# 1.net
KiCad netlist of a schematic drawn in Altium Designer
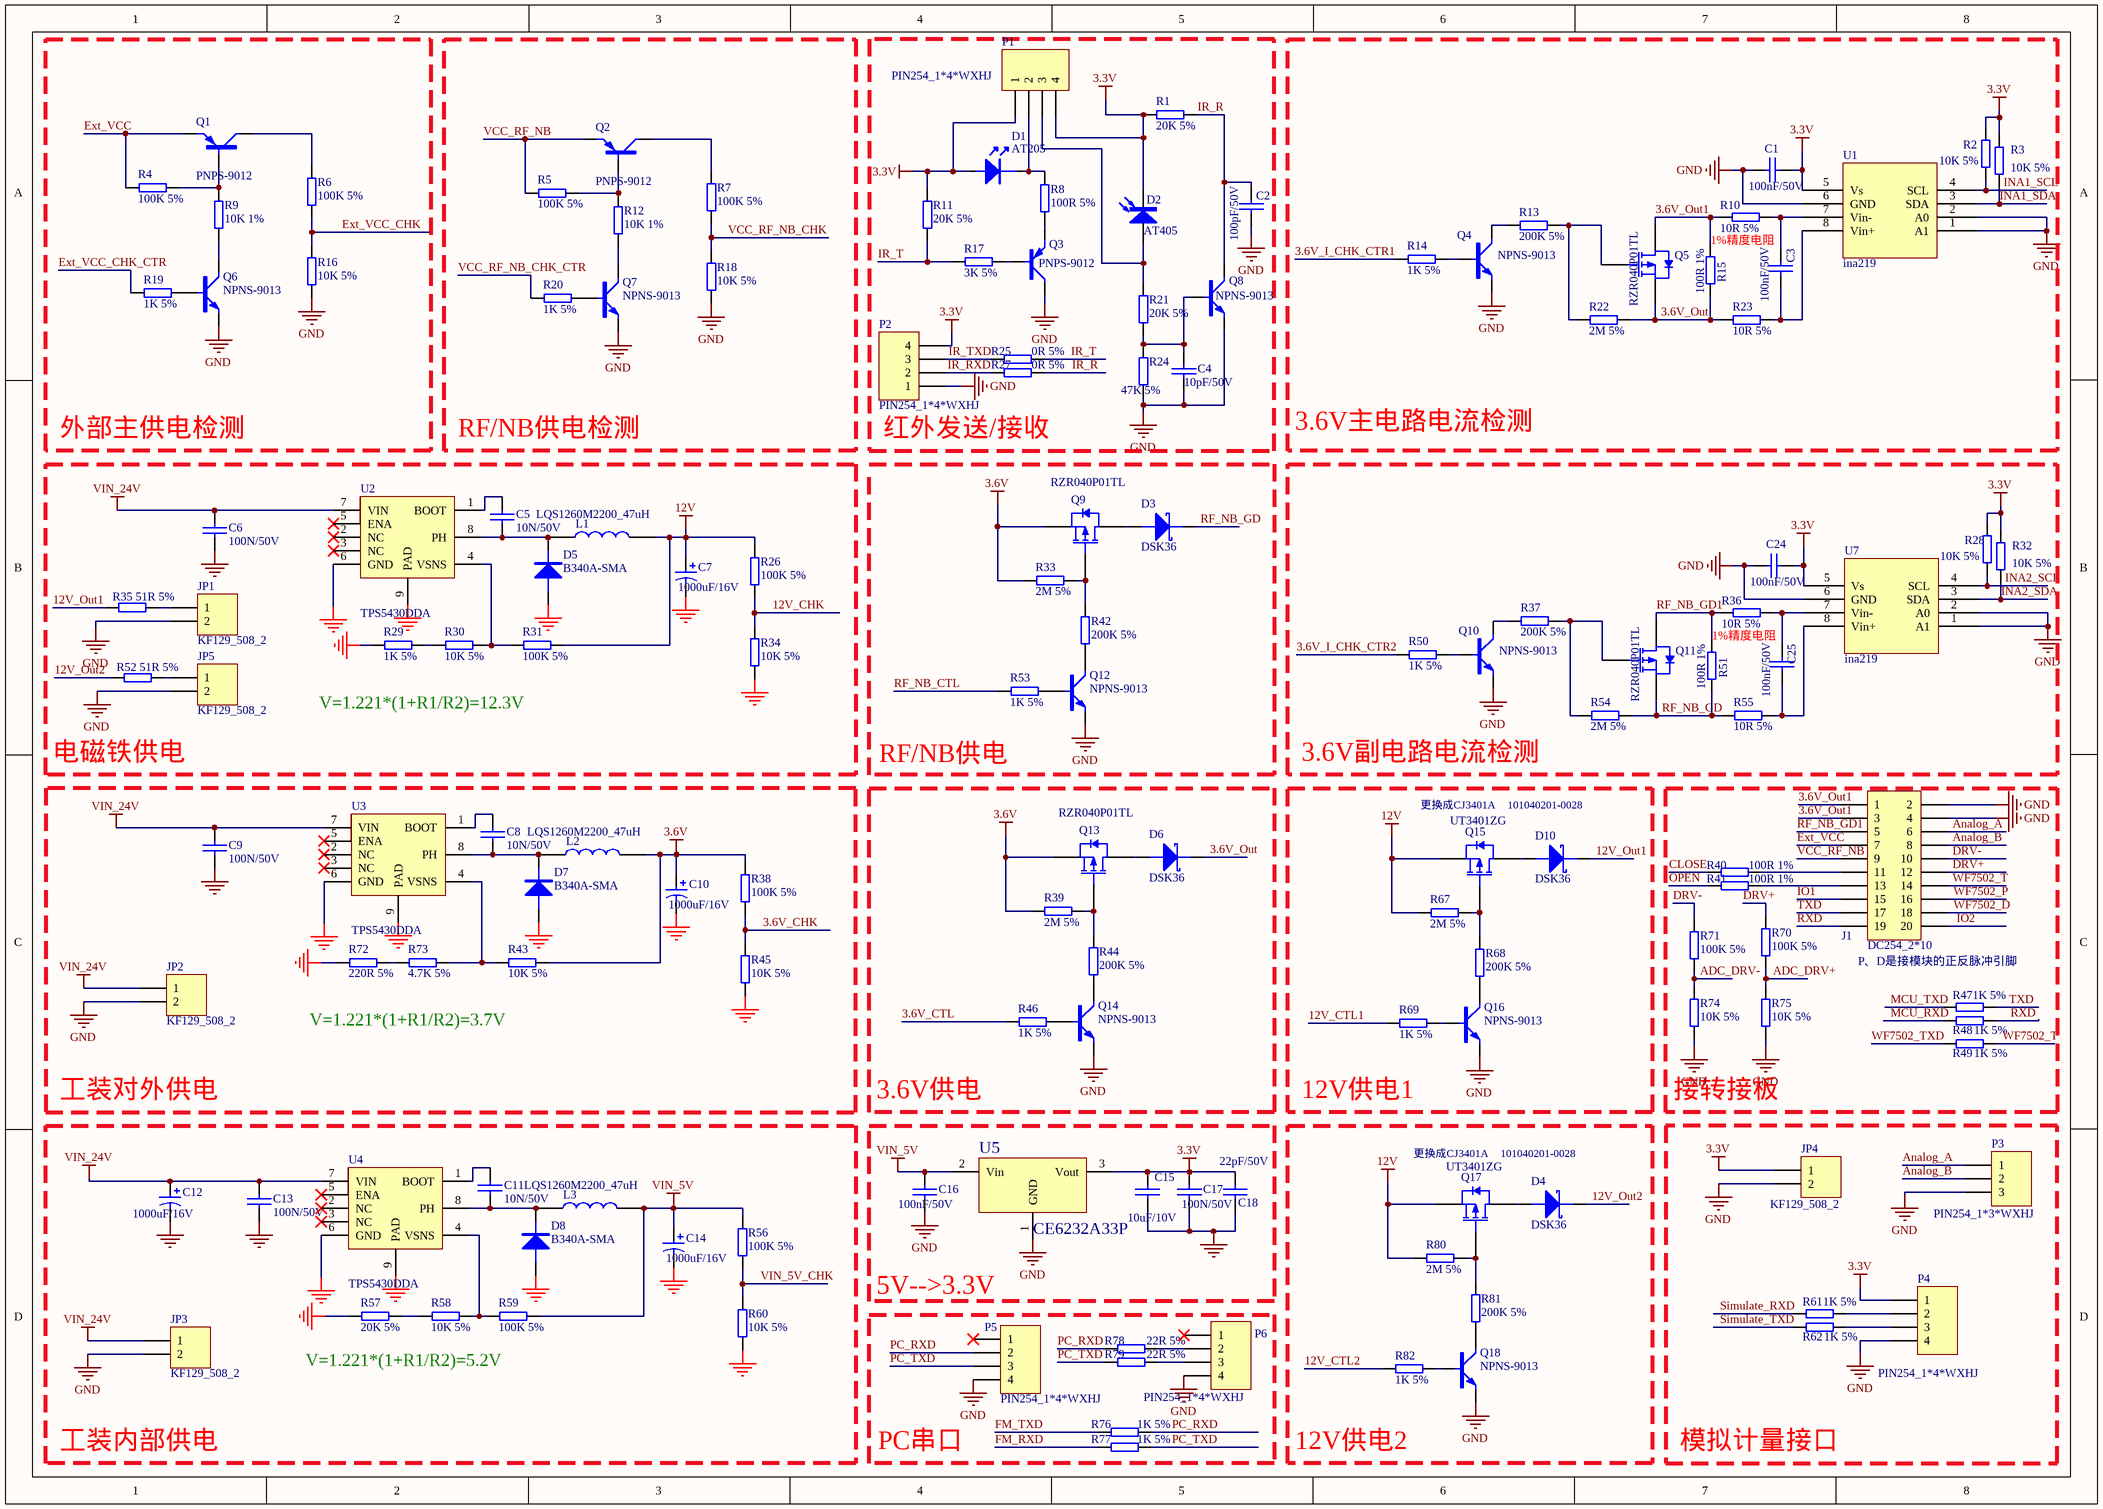
[diagram p0: 水表通用工装一版1.SchDoc]

(export (version "E")
  (design (tool "Eeschema 10.0.6"))
  (components
    (comp (ref "C1")
      (value "100nF/50V")
      (footprint "CAP0603")
      (description "104pF,50 V,±10%,0603,国巨,CC0603KRX7R9BB104")
      (fields (field (name "PART NUMBER") "101020103-0021"))
      (libsource (lib "Database_Libs2") (part "CC03K7R9_100N"))
    )
    (comp (ref "C2")
      (value "100pF/50V")
      (footprint "CAP0603")
      (description "101pf,50 V,±5%,0603,国巨,CC0603JRNP09BN101")
      (fields (field (name "PART NUMBER") "101020103-0010"))
      (libsource (lib "Database_Libs2") (part "CC03JPO9_101P"))
    )
    (comp (ref "C3")
      (value "100nF/50V")
      (footprint "CAP0603")
      (description "104pF,50 V,±10%,0603,国巨,CC0603KRX7R9BB104")
      (fields (field (name "PART NUMBER") "101020103-0021"))
      (libsource (lib "Database_Libs2") (part "CC03K7R9_100N"))
    )
    (comp (ref "C4")
      (value "10pF/50V")
      (footprint "CAP0603")
      (description "10pF,50 V,±5%,0603,X7R,国巨,CC0603JRNPO9BN100")
      (fields (field (name "PART NUMBER") "101020103-0014"))
      (libsource (lib "Database_Libs2") (part "CC03JPO9_10P"))
    )
    (comp (ref "C5")
      (value "10N/50V")
      (footprint "CAP0603")
      (description "10N/50V，±10%，0603")
      (fields (field (name "PART NUMBER") "101020103-0007"))
      (libsource (lib "Database_Libs1") (part "CC03K7R9B_10N"))
    )
    (comp (ref "C6")
      (value "100N/50V")
      (footprint "CAP0603")
      (description "100N/50V，±10%，0603")
      (fields (field (name "PART NUMBER") "101020103-0021"))
      (libsource (lib "Database_Libs1") (part "CC03K7R9B_100N"))
    )
    (comp (ref "C7")
      (value "1000uF/16V")
      (footprint "CAPPC_350_800_1600")
      (description "1000uF,16 V,±20%,8*20mm,Rubycon,16ZLH1000M")
      (fields (field (name "PART NUMBER") "1010203-0029"))
      (libsource (lib "Database_Libs2") (part "CAL7MRZLH_1000U_R"))
    )
    (comp (ref "C8")
      (value "10N/50V")
      (footprint "CAP0603")
      (description "10N/50V，±10%，0603")
      (fields (field (name "PART NUMBER") "101020103-0007"))
      (libsource (lib "Database_Libs1") (part "CC03K7R9B_10N"))
    )
    (comp (ref "C9")
      (value "100N/50V")
      (footprint "CAP0603")
      (description "100N/50V，±10%，0603")
      (fields (field (name "PART NUMBER") "101020103-0021"))
      (libsource (lib "Database_Libs1") (part "CC03K7R9B_100N"))
    )
    (comp (ref "C10")
      (value "1000uF/16V")
      (footprint "CAPPC_350_800_1600")
      (description "1000uF,16 V,±20%,8*20mm,Rubycon,16ZLH1000M")
      (fields (field (name "PART NUMBER") "1010203-0029"))
      (libsource (lib "Database_Libs2") (part "CAL7MRZLH_1000U_R"))
    )
    (comp (ref "C11")
      (value "10N/50V")
      (footprint "CAP0603")
      (description "10N/50V，±10%，0603")
      (fields (field (name "PART NUMBER") "101020103-0007"))
      (libsource (lib "Database_Libs1") (part "CC03K7R9B_10N"))
    )
    (comp (ref "C12")
      (value "1000uF/16V")
      (footprint "CAPPC_350_800_1600")
      (description "1000uF,16 V,±20%,8*20mm,Rubycon,16ZLH1000M")
      (fields (field (name "PART NUMBER") "1010203-0029"))
      (libsource (lib "Database_Libs2") (part "CAL7MRZLH_1000U_R"))
    )
    (comp (ref "C13")
      (value "100N/50V")
      (footprint "CAP0603")
      (description "100N/50V，±10%，0603")
      (fields (field (name "PART NUMBER") "101020103-0021"))
      (libsource (lib "Database_Libs1") (part "CC03K7R9B_100N"))
    )
    (comp (ref "C14")
      (value "1000uF/16V")
      (footprint "CAPPC_350_800_1600")
      (description "1000uF,16 V,±20%,8*20mm,Rubycon,16ZLH1000M")
      (fields (field (name "PART NUMBER") "1010203-0029"))
      (libsource (lib "Database_Libs2") (part "CAL7MRZLH_1000U_R"))
    )
    (comp (ref "C15")
      (value "10uF/10V")
      (footprint "CAP0603")
      (description "106pF,10 V,±10%,0603,村田,GRM188R61A106KE47D")
      (fields (field (name "PART NUMBER") "101020103-0026"))
      (libsource (lib "Database_Libs2") (part "CC03K5R6_10U"))
    )
    (comp (ref "C16")
      (value "100nF/50V")
      (footprint "CAP0603")
      (description "104pF,50 V,±10%,0603,国巨,CC0603KRX7R9BB104")
      (fields (field (name "PART NUMBER") "101020103-0021"))
      (libsource (lib "Database_Libs2") (part "CC03K7R9_100N"))
    )
    (comp (ref "C17")
      (value "100N/50V")
      (footprint "CAP0603")
      (description "100N/50V，±10%，0603")
      (fields (field (name "PART NUMBER") "101020103-0021"))
      (libsource (lib "Database_Libs2") (part "CC03K7R9B_100N"))
    )
    (comp (ref "C18")
      (value "22pF/50V")
      (footprint "CAP0603")
      (description "22pF,50 V,±5%,0603,国巨,CC0603JRNPO9BN22")
      (fields (field (name "PART NUMBER") "101020103-0009"))
      (libsource (lib "Database_Libs2") (part "CC03JPO9_22P"))
    )
    (comp (ref "C24")
      (value "100nF/50V")
      (footprint "CAP0603")
      (description "104pF,50 V,±10%,0603,国巨,CC0603KRX7R9BB104")
      (fields (field (name "PART NUMBER") "101020103-0021"))
      (libsource (lib "Database_Libs2") (part "CC03K7R9_100N"))
    )
    (comp (ref "C25")
      (value "100nF/50V")
      (footprint "CAP0603")
      (description "104pF,50 V,±10%,0603,国巨,CC0603KRX7R9BB104")
      (fields (field (name "PART NUMBER") "101020103-0021"))
      (libsource (lib "Database_Libs2") (part "CC03K7R9_100N"))
    )
    (comp (ref "D1") (value "AT205") (footprint "AT205/405") (libsource (lib "Schlib1") (part "AT205")))
    (comp (ref "D2")
      (value "AT405")
      (footprint "AT205/405")
      (description "红外接收头，插件，红光，AT405_PD_01")
      (fields (field (name "PART NUMBER") "101040102-0011") (field (name "MANUFACTURER") "品观"))
      (libsource (lib "Devices") (part "LED_IN"))
    )
    (comp (ref "D3")
      (value "DSK36")
      (footprint "SOD-123FL")
      (description "DSK14,SOD-123FL,1 A,40 V,28 V,台湾强茂集团苏州群鑫电子,DSK14")
      (fields (field (name "PART NUMBER") "101040101-0043"))
      (libsource (lib "Database_Libs2") (part "02_DSK14"))
    )
    (comp (ref "D4")
      (value "DSK36")
      (footprint "SOD-123FL")
      (description "DSK14,SOD-123FL,1 A,40 V,28 V,台湾强茂集团苏州群鑫电子,DSK14")
      (fields (field (name "PART NUMBER") "101040101-0043"))
      (libsource (lib "Database_Libs2") (part "02_DSK14"))
    )
    (comp (ref "D5")
      (value "B340A-SMA")
      (footprint "DO-214AC")
      (fields (field (name "PART NUMBER") "101040101-0014"))
      (libsource (lib "Database_Libs1") (part "02_B340A-SMA"))
    )
    (comp (ref "D6")
      (value "DSK36")
      (footprint "SOD-123FL")
      (description "DSK14,SOD-123FL,1 A,40 V,28 V,台湾强茂集团苏州群鑫电子,DSK14")
      (fields (field (name "PART NUMBER") "101040101-0043"))
      (libsource (lib "Database_Libs2") (part "02_DSK14"))
    )
    (comp (ref "D7")
      (value "B340A-SMA")
      (footprint "DO-214AC")
      (fields (field (name "PART NUMBER") "101040101-0014"))
      (libsource (lib "Database_Libs1") (part "02_B340A-SMA"))
    )
    (comp (ref "D8")
      (value "B340A-SMA")
      (footprint "DO-214AC")
      (fields (field (name "PART NUMBER") "101040101-0014"))
      (libsource (lib "Database_Libs1") (part "02_B340A-SMA"))
    )
    (comp (ref "D10")
      (value "DSK36")
      (footprint "SOD-123FL")
      (description "DSK14,SOD-123FL,1 A,40 V,28 V,台湾强茂集团苏州群鑫电子,DSK14")
      (fields (field (name "PART NUMBER") "101040101-0043"))
      (libsource (lib "Database_Libs2") (part "02_DSK14"))
    )
    (comp (ref "J1")
      (value "DC254_2*10")
      (footprint "DC254_2*10")
      (description "DC2 2.54mm 2x10pin,2.54mm间距，2x10pin，32×8.55×27.5mm,母头,双排,双排牛角座")
      (fields (field (name "PART NUMBER") "1010902-0139"))
      (libsource (lib "Database_Libs2") (part "DC254_2*10"))
    )
    (comp (ref "JP1")
      (value "KF129_508_2")
      (footprint "KF129_508_2")
      (description "KF129-2P,螺丝紧固,2,ABS,松涛")
      (fields (field (name "PART NUMBER") "1010904-0015"))
      (libsource (lib "Database_Libs2") (part "KF129_508_2"))
    )
    (comp (ref "JP2")
      (value "KF129_508_2")
      (footprint "KF129_508_2")
      (description "KF129-2P,螺丝紧固,2,ABS,松涛")
      (fields (field (name "PART NUMBER") "1010904-0015"))
      (libsource (lib "Database_Libs2") (part "KF129_508_2"))
    )
    (comp (ref "JP3")
      (value "KF129_508_2")
      (footprint "KF129_508_2")
      (description "KF129-2P,螺丝紧固,2,ABS,松涛")
      (fields (field (name "PART NUMBER") "1010904-0015"))
      (libsource (lib "Database_Libs2") (part "KF129_508_2"))
    )
    (comp (ref "JP4")
      (value "KF129_508_2")
      (footprint "KF129_508_2")
      (description "KF129-2P,螺丝紧固,2,ABS,松涛")
      (fields (field (name "PART NUMBER") "1010904-0015"))
      (libsource (lib "Database_Libs2") (part "KF129_508_2"))
    )
    (comp (ref "JP5")
      (value "KF129_508_2")
      (footprint "KF129_508_2")
      (description "KF129-2P,螺丝紧固,2,ABS,松涛")
      (fields (field (name "PART NUMBER") "1010904-0015"))
      (libsource (lib "Database_Libs2") (part "KF129_508_2"))
    )
    (comp (ref "L1")
      (value "LQS1260M2200_47uH")
      (footprint "LQS1212")
      (description "47uH/2.2A,±20%，0.072Ω，L1200X1200X600")
      (fields (field (name "PART NUMBER") "1010302-0007"))
      (libsource (lib "Database_Libs1") (part "06_LQS1260M2200_47uH"))
    )
    (comp (ref "L2")
      (value "LQS1260M2200_47uH")
      (footprint "LQS1212")
      (description "47uH/2.2A,±20%，0.072Ω，L1200X1200X600")
      (fields (field (name "PART NUMBER") "1010302-0007"))
      (libsource (lib "Database_Libs1") (part "06_LQS1260M2200_47uH"))
    )
    (comp (ref "L3")
      (value "LQS1260M2200_47uH")
      (footprint "LQS1212")
      (description "47uH/2.2A,±20%，0.072Ω，L1200X1200X600")
      (fields (field (name "PART NUMBER") "1010302-0007"))
      (libsource (lib "Database_Libs1") (part "06_LQS1260M2200_47uH"))
    )
    (comp (ref "P1")
      (value "PIN254_1*4*WXHJ")
      (footprint "PIN254_1*4*1100S")
      (description "1*4 ，Φ1.0 ，2.54mm，直脚,无需焊接器件")
      (fields (field (name "PART NUMBER") "AD_WXHJ_PinHeader_01"))
      (libsource (lib "Database_Libs2") (part "PIN254_1*4*1100S"))
    )
    (comp (ref "P2")
      (value "PIN254_1*4*WXHJ")
      (footprint "PIN254_1*4*1100S")
      (description "1*4 ，Φ1.0 ，2.54mm，直脚,无需焊接器件")
      (fields (field (name "PART NUMBER") "AD_WXHJ_PinHeader_01"))
      (libsource (lib "") (part "PIN254_1*4*1100S_2"))
    )
    (comp (ref "P3")
      (value "PIN254_1*3*WXHJ")
      (footprint "PIN254_1*3*1100S - duplicate")
      (description "1*3 ，Φ1.0 ，2.54mm，直脚,无需焊接器件")
      (fields (field (name "PART NUMBER") "AD_WXHJ_PinHeader_01"))
      (libsource (lib "模拟计量") (part "PIN254_1*3*1100S"))
    )
    (comp (ref "P4")
      (value "PIN254_1*4*WXHJ")
      (footprint "PIN254_1*4*1100S")
      (description "1*4 ，Φ1.0 ，2.54mm，直脚,无需焊接器件")
      (fields (field (name "PART NUMBER") "AD_WXHJ_PinHeader_01"))
      (libsource (lib "") (part "PIN254_1*4*1100S_1"))
    )
    (comp (ref "P5")
      (value "PIN254_1*4*WXHJ")
      (footprint "PIN254_1*4*1100S")
      (description "1*4 ，Φ1.0 ，2.54mm，直脚,无需焊接器件")
      (fields (field (name "PART NUMBER") "AD_WXHJ_PinHeader_01"))
      (libsource (lib "") (part "PIN254_1*4*1100S_1"))
    )
    (comp (ref "P6")
      (value "PIN254_1*4*WXHJ")
      (footprint "PIN254_1*4*1100S")
      (description "1*4 ，Φ1.0 ，2.54mm，直脚,无需焊接器件")
      (fields (field (name "PART NUMBER") "AD_WXHJ_PinHeader_01"))
      (libsource (lib "") (part "PIN254_1*4*1100S_1"))
    )
    (comp (ref "Q1")
      (value "PNPS-9012")
      (footprint "SOT-23")
      (description "9012,PNP,SOT-23,JCET;长电,S9012")
      (fields (field (name "PART NUMBER") "101040201-0001"))
      (libsource (lib "Database_Libs2") (part "03_PNPS-9012"))
    )
    (comp (ref "Q2")
      (value "PNPS-9012")
      (footprint "SOT-23")
      (description "9012,PNP,SOT-23,JCET;长电,S9012")
      (fields (field (name "PART NUMBER") "101040201-0001"))
      (libsource (lib "Database_Libs2") (part "03_PNPS-9012"))
    )
    (comp (ref "Q3")
      (value "PNPS-9012")
      (footprint "SOT-23")
      (description "9012,PNP,SOT-23,JCET;长电,S9012")
      (fields (field (name "PART NUMBER") "101040201-0001"))
      (libsource (lib "Database_Libs2") (part "03_PNPS-9012"))
    )
    (comp (ref "Q4")
      (value "NPNS-9013")
      (footprint "SOT-23")
      (description "9013,NPN,SOT-23,长电,S9013")
      (fields (field (name "PART NUMBER") "101040201-0002"))
      (libsource (lib "Database_Libs2") (part "03_NPNS-9013"))
    )
    (comp (ref "Q5")
      (value "RZR040P01TL")
      (footprint "SOT-23")
      (description "RZR040P01TL；1.5v导通,P-MOS,SOT-23,罗姆,RZR040P01TL")
      (fields (field (name "PART NUMBER") "101040201-0010"))
      (libsource (lib "Database_Libs2") (part "03_P-RZR040P01TL"))
    )
    (comp (ref "Q6")
      (value "NPNS-9013")
      (footprint "SOT-23")
      (description "9013,NPN,SOT-23,长电,S9013")
      (fields (field (name "PART NUMBER") "101040201-0002"))
      (libsource (lib "Database_Libs2") (part "03_NPNS-9013"))
    )
    (comp (ref "Q7")
      (value "NPNS-9013")
      (footprint "SOT-23")
      (description "9013,NPN,SOT-23,长电,S9013")
      (fields (field (name "PART NUMBER") "101040201-0002"))
      (libsource (lib "Database_Libs2") (part "03_NPNS-9013"))
    )
    (comp (ref "Q8")
      (value "NPNS-9013")
      (footprint "SOT-23")
      (description "9013,NPN,SOT-23,长电,S9013")
      (fields (field (name "PART NUMBER") "101040201-0002"))
      (libsource (lib "Database_Libs2") (part "03_NPNS-9013"))
    )
    (comp (ref "Q9")
      (value "RZR040P01TL")
      (footprint "SOT-23")
      (description "RZR040P01TL；1.5v导通,P-MOS,SOT-23,罗姆,RZR040P01TL")
      (fields (field (name "PART NUMBER") "101040201-0010"))
      (libsource (lib "Database_Libs2") (part "03_P-RZR040P01TL"))
    )
    (comp (ref "Q10")
      (value "NPNS-9013")
      (footprint "SOT-23")
      (description "9013,NPN,SOT-23,长电,S9013")
      (fields (field (name "PART NUMBER") "101040201-0002"))
      (libsource (lib "Database_Libs2") (part "03_NPNS-9013"))
    )
    (comp (ref "Q11")
      (value "RZR040P01TL")
      (footprint "SOT-23")
      (description "RZR040P01TL；1.5v导通,P-MOS,SOT-23,罗姆,RZR040P01TL")
      (fields (field (name "PART NUMBER") "101040201-0010"))
      (libsource (lib "Database_Libs2") (part "03_P-RZR040P01TL"))
    )
    (comp (ref "Q12")
      (value "NPNS-9013")
      (footprint "SOT-23")
      (description "9013,NPN,SOT-23,长电,S9013")
      (fields (field (name "PART NUMBER") "101040201-0002"))
      (libsource (lib "Database_Libs2") (part "03_NPNS-9013"))
    )
    (comp (ref "Q13")
      (value "RZR040P01TL")
      (footprint "SOT-23")
      (description "RZR040P01TL；1.5v导通,P-MOS,SOT-23,罗姆,RZR040P01TL")
      (fields (field (name "PART NUMBER") "101040201-0010"))
      (libsource (lib "Database_Libs2") (part "03_P-RZR040P01TL"))
    )
    (comp (ref "Q14")
      (value "NPNS-9013")
      (footprint "SOT-23")
      (description "9013,NPN,SOT-23,长电,S9013")
      (fields (field (name "PART NUMBER") "101040201-0002"))
      (libsource (lib "Database_Libs2") (part "03_NPNS-9013"))
    )
    (comp (ref "Q15")
      (value "UT3401ZG")
      (footprint "SOT-23")
      (description "UT3401ZG,P-MOS,SOT-23,UTC,UT3401ZG")
      (fields (field (name "PART NUMBER") "101040201-0013"))
      (libsource (lib "Database_Libs2") (part "03_P-UT3401ZG"))
    )
    (comp (ref "Q16")
      (value "NPNS-9013")
      (footprint "SOT-23")
      (description "9013,NPN,SOT-23,长电,S9013")
      (fields (field (name "PART NUMBER") "101040201-0002"))
      (libsource (lib "Database_Libs2") (part "03_NPNS-9013"))
    )
    (comp (ref "Q17")
      (value "UT3401ZG")
      (footprint "SOT-23")
      (description "UT3401ZG,P-MOS,SOT-23,UTC,UT3401ZG")
      (fields (field (name "PART NUMBER") "101040201-0013"))
      (libsource (lib "Database_Libs2") (part "03_P-UT3401ZG"))
    )
    (comp (ref "Q18")
      (value "NPNS-9013")
      (footprint "SOT-23")
      (description "9013,NPN,SOT-23,长电,S9013")
      (fields (field (name "PART NUMBER") "101040201-0002"))
      (libsource (lib "Database_Libs2") (part "03_NPNS-9013"))
    )
    (comp (ref "R1")
      (value "20K 5%")
      (footprint "RES0603")
      (description "国巨,±5%,0603,,155 ℃,-55 ℃,RC0603JR-0720KL,无铅,200 ppm/℃,1/10W,,20K")
      (fields (field (name "PART NUMBER") "101010103-0004"))
      (libsource (lib "Database_Libs2") (part "RC03J_20K"))
    )
    (comp (ref "R2")
      (value "10K 5%")
      (footprint "RES0603")
      (description "国巨,±5%,0603,,155 ℃,-55 ℃,RC0603JR-0710KL,无铅,200 ppm/℃,1/10W,,10K")
      (fields (field (name "PART NUMBER") "101010103-0003"))
      (libsource (lib "Database_Libs2") (part "RC03J_10K"))
    )
    (comp (ref "R3")
      (value "10K 5%")
      (footprint "RES0603")
      (description "国巨,±5%,0603,,155 ℃,-55 ℃,RC0603JR-0710KL,无铅,200 ppm/℃,1/10W,,10K")
      (fields (field (name "PART NUMBER") "101010103-0003"))
      (libsource (lib "Database_Libs2") (part "RC03J_10K"))
    )
    (comp (ref "R4")
      (value "100K 5%")
      (footprint "RES0603")
      (description "国巨,±5%,0603,,155 ℃,-55 ℃,RC0603JR-07100KL,无铅,100 ppm/℃,1/10W,,100K")
      (fields (field (name "PART NUMBER") "101010103-0005"))
      (libsource (lib "Database_Libs2") (part "RC03J_100K"))
    )
    (comp (ref "R5")
      (value "100K 5%")
      (footprint "RES0603")
      (description "国巨,±5%,0603,,155 ℃,-55 ℃,RC0603JR-07100KL,无铅,100 ppm/℃,1/10W,,100K")
      (fields (field (name "PART NUMBER") "101010103-0005"))
      (libsource (lib "Database_Libs2") (part "RC03J_100K"))
    )
    (comp (ref "R6")
      (value "100K 5%")
      (footprint "RES0603")
      (description "国巨,±5%,0603,,155 ℃,-55 ℃,RC0603JR-07100KL,无铅,100 ppm/℃,1/10W,,100K")
      (fields (field (name "PART NUMBER") "101010103-0005"))
      (libsource (lib "Database_Libs2") (part "RC03J_100K"))
    )
    (comp (ref "R7")
      (value "100K 5%")
      (footprint "RES0603")
      (description "国巨,±5%,0603,,155 ℃,-55 ℃,RC0603JR-07100KL,无铅,100 ppm/℃,1/10W,,100K")
      (fields (field (name "PART NUMBER") "101010103-0005"))
      (libsource (lib "Database_Libs2") (part "RC03J_100K"))
    )
    (comp (ref "R8")
      (value "100R 5%")
      (footprint "RES0603")
      (description "100R,±5%,1/10W,0603,国巨,RC0603JR-07100RL")
      (fields (field (name "PART NUMBER") "101010103-0022"))
      (libsource (lib "Database_Libs2") (part "RC03J_100R"))
    )
    (comp (ref "R9")
      (value "10K 1%")
      (footprint "RES0603")
      (description "10K±1%,1/10W,0603")
      (fields (field (name "PART NUMBER") "101010103-0052"))
      (libsource (lib "Database_Libs2") (part "RC03J_10K"))
    )
    (comp (ref "R10")
      (value "10R 5%")
      (footprint "RES0603")
      (description "10R,±5%,1/10W,0603,国巨,RC0603JR-0710RL")
      (fields (field (name "PART NUMBER") "101010103-0017"))
      (libsource (lib "Database_Libs2") (part "RC03J_10R"))
    )
    (comp (ref "R11")
      (value "20K 5%")
      (footprint "RES0603")
      (description "国巨,±5%,0603,,155 ℃,-55 ℃,RC0603JR-0720KL,无铅,200 ppm/℃,1/10W,,20K")
      (fields (field (name "PART NUMBER") "101010103-0004"))
      (libsource (lib "Database_Libs2") (part "RC03J_20K"))
    )
    (comp (ref "R12")
      (value "10K 1%")
      (footprint "RES0603")
      (description "10K±1%,1/10W,0603")
      (fields (field (name "PART NUMBER") "101010103-0052"))
      (libsource (lib "Database_Libs2") (part "RC03J_10K"))
    )
    (comp (ref "R13")
      (value "200K 5%")
      (footprint "RES0603")
      (description "200K,±5%,1/10W,0603,国巨,RC0603JR-07200KL")
      (fields (field (name "PART NUMBER") "101010103-0034"))
      (libsource (lib "Database_Libs2") (part "RC03J_200K"))
    )
    (comp (ref "R14")
      (value "1K 5%")
      (footprint "RES0603")
      (description "1K,±5%,1/10W,0603,国巨,RC0603JR-071KL")
      (fields (field (name "PART NUMBER") "101010103-0008"))
      (libsource (lib "Database_Libs2") (part "RC03J_1K"))
    )
    (comp (ref "R15")
      (value "100R 1%")
      (footprint "RES0603")
      (description "100Ω,±1%,1/10W,0603,国巨股份有限公司,RC0603FR-07100RL")
      (fields (field (name "PART NUMBER") "101010103-0041"))
      (libsource (lib "Database_Libs2") (part "RC03J_100R"))
    )
    (comp (ref "R16")
      (value "10K 5%")
      (footprint "RES0603")
      (description "国巨,±5%,0603,,155 ℃,-55 ℃,RC0603JR-0710KL,无铅,200 ppm/℃,1/10W,,10K")
      (fields (field (name "PART NUMBER") "101010103-0003"))
      (libsource (lib "Database_Libs2") (part "RC03J_10K"))
    )
    (comp (ref "R17")
      (value "3K 5%")
      (footprint "RES0603")
      (description "国巨,±5%,0603,,155 ℃,-55 ℃,RC0603JR-073KL,无铅,100 ppm/℃,1/10W,,3K")
      (fields (field (name "PART NUMBER") "101010103-0006"))
      (libsource (lib "Database_Libs2") (part "RC03J_3K"))
    )
    (comp (ref "R18")
      (value "10K 5%")
      (footprint "RES0603")
      (description "国巨,±5%,0603,,155 ℃,-55 ℃,RC0603JR-0710KL,无铅,200 ppm/℃,1/10W,,10K")
      (fields (field (name "PART NUMBER") "101010103-0003"))
      (libsource (lib "Database_Libs2") (part "RC03J_10K"))
    )
    (comp (ref "R19")
      (value "1K 5%")
      (footprint "RES0603")
      (description "1K,±5%,1/10W,0603,国巨,RC0603JR-071KL")
      (fields (field (name "PART NUMBER") "101010103-0008"))
      (libsource (lib "Database_Libs2") (part "RC03J_1K"))
    )
    (comp (ref "R20")
      (value "1K 5%")
      (footprint "RES0603")
      (description "1K,±5%,1/10W,0603,国巨,RC0603JR-071KL")
      (fields (field (name "PART NUMBER") "101010103-0008"))
      (libsource (lib "Database_Libs2") (part "RC03J_1K"))
    )
    (comp (ref "R21")
      (value "20K 5%")
      (footprint "RES0603")
      (description "国巨,±5%,0603,,155 ℃,-55 ℃,RC0603JR-0720KL,无铅,200 ppm/℃,1/10W,,20K")
      (fields (field (name "PART NUMBER") "101010103-0004"))
      (libsource (lib "Database_Libs2") (part "RC03J_20K"))
    )
    (comp (ref "R22")
      (value "2M 5%")
      (footprint "RES0603")
      (description "国巨,±5%,0603,,155 ℃,-55 ℃,RC0603JR-072ML,含铅,100 ppm/℃,1/10W,,2M")
      (fields (field (name "PART NUMBER") "101010103-0025"))
      (libsource (lib "Database_Libs2") (part "RC03J_2M"))
    )
    (comp (ref "R23")
      (value "10R 5%")
      (footprint "RES0603")
      (description "10R,±5%,1/10W,0603,国巨,RC0603JR-0710RL")
      (fields (field (name "PART NUMBER") "101010103-0017"))
      (libsource (lib "Database_Libs2") (part "RC03J_10R"))
    )
    (comp (ref "R24")
      (value "47K 5%")
      (footprint "RES0603")
      (description "47K,±5%,1/10W,0603,国巨,RC0603JR-0747KL")
      (fields (field (name "PART NUMBER") "101010103-0012"))
      (libsource (lib "Database_Libs2") (part "RC03J_47K"))
    )
    (comp (ref "R25")
      (value "0R 5%")
      (footprint "RES0603")
      (description "国巨,±5%,0603,,155 ℃,-55 ℃,RC0603J2-070RL,无铅,200 ppm/℃,1/10W,,0R")
      (fields (field (name "PART NUMBER") "101010103-0001"))
      (libsource (lib "Database_Libs2") (part "RC03J_0R"))
    )
    (comp (ref "R26")
      (value "100K 5%")
      (footprint "RES0603")
      (description "100K±5%,1/10W,0603")
      (fields (field (name "PART NUMBER") "101010103-0005"))
      (libsource (lib "Database_Libs1") (part "RC03JF_100K"))
    )
    (comp (ref "R27")
      (value "0R 5%")
      (footprint "RES0603")
      (description "国巨,±5%,0603,,155 ℃,-55 ℃,RC0603J2-070RL,无铅,200 ppm/℃,1/10W,,0R")
      (fields (field (name "PART NUMBER") "101010103-0001"))
      (libsource (lib "Database_Libs2") (part "RC03J_0R"))
    )
    (comp (ref "R28")
      (value "10K 5%")
      (footprint "RES0603")
      (description "国巨,±5%,0603,,155 ℃,-55 ℃,RC0603JR-0710KL,无铅,200 ppm/℃,1/10W,,10K")
      (fields (field (name "PART NUMBER") "101010103-0003"))
      (libsource (lib "Database_Libs2") (part "RC03J_10K"))
    )
    (comp (ref "R29")
      (value "1K 5%")
      (footprint "RES0603")
      (description "1K,±5%,1/10W,0603,国巨,RC0603JR-071KL")
      (fields (field (name "PART NUMBER") "101010103-0008"))
      (libsource (lib "Database_Libs2") (part "RC03J_1K"))
    )
    (comp (ref "R30")
      (value "10K 5%")
      (footprint "RES0603")
      (description "国巨,±5%,0603,,155 ℃,-55 ℃,RC0603JR-0710KL,无铅,200 ppm/℃,1/10W,,10K")
      (fields (field (name "PART NUMBER") "101010103-0003"))
      (libsource (lib "Database_Libs2") (part "RC03J_10K"))
    )
    (comp (ref "R31")
      (value "100K 5%")
      (footprint "RES0603")
      (description "国巨,±5%,0603,,155 ℃,-55 ℃,RC0603JR-07100KL,无铅,100 ppm/℃,1/10W,,100K")
      (fields (field (name "PART NUMBER") "101010103-0005"))
      (libsource (lib "Database_Libs2") (part "RC03J_100K"))
    )
    (comp (ref "R32")
      (value "10K 5%")
      (footprint "RES0603")
      (description "国巨,±5%,0603,,155 ℃,-55 ℃,RC0603JR-0710KL,无铅,200 ppm/℃,1/10W,,10K")
      (fields (field (name "PART NUMBER") "101010103-0003"))
      (libsource (lib "Database_Libs2") (part "RC03J_10K"))
    )
    (comp (ref "R33")
      (value "2M 5%")
      (footprint "RES0603")
      (description "国巨,±5%,0603,,155 ℃,-55 ℃,RC0603JR-072ML,含铅,100 ppm/℃,1/10W,,2M")
      (fields (field (name "PART NUMBER") "101010103-0025"))
      (libsource (lib "Database_Libs2") (part "RC03J_2M"))
    )
    (comp (ref "R34")
      (value "10K 5%")
      (footprint "RES0603")
      (description "国巨,±5%,0603,,155 ℃,-55 ℃,RC0603JR-0710KL,无铅,200 ppm/℃,1/10W,,10K")
      (fields (field (name "PART NUMBER") "101010103-0003"))
      (libsource (lib "Database_Libs2") (part "RC03J_10K"))
    )
    (comp (ref "R35")
      (value "51R 5%")
      (footprint "RES0603")
      (description "国巨,±5%,0603,,155 ℃,-55 ℃,RC0603JR-0751RL,无铅,100 ppm/℃,1/10W,,51欧")
      (fields (field (name "PART NUMBER") "101010103-0037"))
      (libsource (lib "Database_Libs2") (part "RC03J_51R"))
    )
    (comp (ref "R36")
      (value "10R 5%")
      (footprint "RES0603")
      (description "10R,±5%,1/10W,0603,国巨,RC0603JR-0710RL")
      (fields (field (name "PART NUMBER") "101010103-0017"))
      (libsource (lib "Database_Libs2") (part "RC03J_10R"))
    )
    (comp (ref "R37")
      (value "200K 5%")
      (footprint "RES0603")
      (description "200K,±5%,1/10W,0603,国巨,RC0603JR-07200KL")
      (fields (field (name "PART NUMBER") "101010103-0034"))
      (libsource (lib "Database_Libs2") (part "RC03J_200K"))
    )
    (comp (ref "R38")
      (value "100K 5%")
      (footprint "RES0603")
      (description "100K±5%,1/10W,0603")
      (fields (field (name "PART NUMBER") "101010103-0005"))
      (libsource (lib "Database_Libs1") (part "RC03JF_100K"))
    )
    (comp (ref "R39")
      (value "2M 5%")
      (footprint "RES0603")
      (description "国巨,±5%,0603,,155 ℃,-55 ℃,RC0603JR-072ML,含铅,100 ppm/℃,1/10W,,2M")
      (fields (field (name "PART NUMBER") "101010103-0025"))
      (libsource (lib "Database_Libs2") (part "RC03J_2M"))
    )
    (comp (ref "R40")
      (value "100R 1%")
      (footprint "RES0603")
      (description "100Ω,±1%,1/10W,0603,国巨股份有限公司,RC0603FR-07100RL")
      (fields (field (name "PART NUMBER") "101010103-0041"))
      (libsource (lib "Database_Libs2") (part "RC03J_100R"))
    )
    (comp (ref "R41")
      (value "100R 1%")
      (footprint "RES0603")
      (description "100Ω,±1%,1/10W,0603,国巨股份有限公司,RC0603FR-07100RL")
      (fields (field (name "PART NUMBER") "101010103-0041"))
      (libsource (lib "Database_Libs2") (part "RC03J_100R"))
    )
    (comp (ref "R42")
      (value "200K 5%")
      (footprint "RES0603")
      (description "200K,±5%,1/10W,0603,国巨,RC0603JR-07200KL")
      (fields (field (name "PART NUMBER") "101010103-0034"))
      (libsource (lib "Database_Libs2") (part "RC03J_200K"))
    )
    (comp (ref "R43")
      (value "10K 5%")
      (footprint "RES0603")
      (description "国巨,±5%,0603,,155 ℃,-55 ℃,RC0603JR-0710KL,无铅,200 ppm/℃,1/10W,,10K")
      (fields (field (name "PART NUMBER") "101010103-0003"))
      (libsource (lib "Database_Libs2") (part "RC03J_10K"))
    )
    (comp (ref "R44")
      (value "200K 5%")
      (footprint "RES0603")
      (description "200K,±5%,1/10W,0603,国巨,RC0603JR-07200KL")
      (fields (field (name "PART NUMBER") "101010103-0034"))
      (libsource (lib "Database_Libs2") (part "RC03J_200K"))
    )
    (comp (ref "R45")
      (value "10K 5%")
      (footprint "RES0603")
      (description "国巨,±5%,0603,,155 ℃,-55 ℃,RC0603JR-0710KL,无铅,200 ppm/℃,1/10W,,10K")
      (fields (field (name "PART NUMBER") "101010103-0003"))
      (libsource (lib "Database_Libs2") (part "RC03J_10K"))
    )
    (comp (ref "R46")
      (value "1K 5%")
      (footprint "RES0603")
      (description "1K,±5%,1/10W,0603,国巨,RC0603JR-071KL")
      (fields (field (name "PART NUMBER") "101010103-0008"))
      (libsource (lib "Database_Libs2") (part "RC03J_1K"))
    )
    (comp (ref "R47")
      (value "1K 5%")
      (footprint "RES0603")
      (description "1K,±5%,1/10W,0603,国巨,RC0603JR-071KL")
      (fields (field (name "PART NUMBER") "101010103-0008"))
      (libsource (lib "Database_Libs2") (part "RC03J_1K"))
    )
    (comp (ref "R48")
      (value "1K 5%")
      (footprint "RES0603")
      (description "1K,±5%,1/10W,0603,国巨,RC0603JR-071KL")
      (fields (field (name "PART NUMBER") "101010103-0008"))
      (libsource (lib "Database_Libs2") (part "RC03J_1K"))
    )
    (comp (ref "R49")
      (value "1K 5%")
      (footprint "RES0603")
      (description "1K,±5%,1/10W,0603,国巨,RC0603JR-071KL")
      (fields (field (name "PART NUMBER") "101010103-0008"))
      (libsource (lib "Database_Libs2") (part "RC03J_1K"))
    )
    (comp (ref "R50")
      (value "1K 5%")
      (footprint "RES0603")
      (description "1K,±5%,1/10W,0603,国巨,RC0603JR-071KL")
      (fields (field (name "PART NUMBER") "101010103-0008"))
      (libsource (lib "Database_Libs2") (part "RC03J_1K"))
    )
    (comp (ref "R51")
      (value "100R 1%")
      (footprint "RES0603")
      (description "100Ω,±1%,1/10W,0603,国巨股份有限公司,RC0603FR-07100RL")
      (fields (field (name "PART NUMBER") "101010103-0041"))
      (libsource (lib "Database_Libs2") (part "RC03J_100R"))
    )
    (comp (ref "R52")
      (value "51R 5%")
      (footprint "RES0603")
      (description "国巨,±5%,0603,,155 ℃,-55 ℃,RC0603JR-0751RL,无铅,100 ppm/℃,1/10W,,51欧")
      (fields (field (name "PART NUMBER") "101010103-0037"))
      (libsource (lib "Database_Libs2") (part "RC03J_51R"))
    )
    (comp (ref "R53")
      (value "1K 5%")
      (footprint "RES0603")
      (description "1K,±5%,1/10W,0603,国巨,RC0603JR-071KL")
      (fields (field (name "PART NUMBER") "101010103-0008"))
      (libsource (lib "Database_Libs2") (part "RC03J_1K"))
    )
    (comp (ref "R54")
      (value "2M 5%")
      (footprint "RES0603")
      (description "国巨,±5%,0603,,155 ℃,-55 ℃,RC0603JR-072ML,含铅,100 ppm/℃,1/10W,,2M")
      (fields (field (name "PART NUMBER") "101010103-0025"))
      (libsource (lib "Database_Libs2") (part "RC03J_2M"))
    )
    (comp (ref "R55")
      (value "10R 5%")
      (footprint "RES0603")
      (description "10R,±5%,1/10W,0603,国巨,RC0603JR-0710RL")
      (fields (field (name "PART NUMBER") "101010103-0017"))
      (libsource (lib "Database_Libs2") (part "RC03J_10R"))
    )
    (comp (ref "R56")
      (value "100K 5%")
      (footprint "RES0603")
      (description "100K±5%,1/10W,0603")
      (fields (field (name "PART NUMBER") "101010103-0005"))
      (libsource (lib "Database_Libs1") (part "RC03JF_100K"))
    )
    (comp (ref "R57")
      (value "20K 5%")
      (footprint "RES0603")
      (description "国巨,±5%,0603,,155 ℃,-55 ℃,RC0603JR-0720KL,无铅,200 ppm/℃,1/10W,,20K")
      (fields (field (name "PART NUMBER") "101010103-0004"))
      (libsource (lib "Database_Libs2") (part "RC03J_20K"))
    )
    (comp (ref "R58")
      (value "10K 5%")
      (footprint "RES0603")
      (description "国巨,±5%,0603,,155 ℃,-55 ℃,RC0603JR-0710KL,无铅,200 ppm/℃,1/10W,,10K")
      (fields (field (name "PART NUMBER") "101010103-0003"))
      (libsource (lib "Database_Libs2") (part "RC03J_10K"))
    )
    (comp (ref "R59")
      (value "100K 5%")
      (footprint "RES0603")
      (description "100K±5%,1/10W,0603")
      (fields (field (name "PART NUMBER") "101010103-0005"))
      (libsource (lib "Database_Libs1") (part "RC03JF_100K"))
    )
    (comp (ref "R60")
      (value "10K 5%")
      (footprint "RES0603")
      (description "国巨,±5%,0603,,155 ℃,-55 ℃,RC0603JR-0710KL,无铅,200 ppm/℃,1/10W,,10K")
      (fields (field (name "PART NUMBER") "101010103-0003"))
      (libsource (lib "Database_Libs2") (part "RC03J_10K"))
    )
    (comp (ref "R61")
      (value "1K 5%")
      (footprint "RES0603")
      (description "1K,±5%,1/10W,0603,国巨,RC0603JR-071KL")
      (fields (field (name "PART NUMBER") "101010103-0008"))
      (libsource (lib "Database_Libs2") (part "RC03J_1K"))
    )
    (comp (ref "R62")
      (value "1K 5%")
      (footprint "RES0603")
      (description "1K,±5%,1/10W,0603,国巨,RC0603JR-071KL")
      (fields (field (name "PART NUMBER") "101010103-0008"))
      (libsource (lib "Database_Libs2") (part "RC03J_1K"))
    )
    (comp (ref "R67")
      (value "2M 5%")
      (footprint "RES0603")
      (description "国巨,±5%,0603,,155 ℃,-55 ℃,RC0603JR-072ML,含铅,100 ppm/℃,1/10W,,2M")
      (fields (field (name "PART NUMBER") "101010103-0025"))
      (libsource (lib "Database_Libs2") (part "RC03J_2M"))
    )
    (comp (ref "R68")
      (value "200K 5%")
      (footprint "RES0603")
      (description "200K,±5%,1/10W,0603,国巨,RC0603JR-07200KL")
      (fields (field (name "PART NUMBER") "101010103-0034"))
      (libsource (lib "Database_Libs2") (part "RC03J_200K"))
    )
    (comp (ref "R69")
      (value "1K 5%")
      (footprint "RES0603")
      (description "1K,±5%,1/10W,0603,国巨,RC0603JR-071KL")
      (fields (field (name "PART NUMBER") "101010103-0008"))
      (libsource (lib "Database_Libs2") (part "RC03J_1K"))
    )
    (comp (ref "R70")
      (value "100K 5%")
      (footprint "RES0603")
      (description "100K±5%,1/10W,0603")
      (fields (field (name "PART NUMBER") "101010103-0005"))
      (libsource (lib "Database_Libs1") (part "RC03JF_100K"))
    )
    (comp (ref "R71")
      (value "100K 5%")
      (footprint "RES0603")
      (description "100K±5%,1/10W,0603")
      (fields (field (name "PART NUMBER") "101010103-0005"))
      (libsource (lib "Database_Libs1") (part "RC03JF_100K"))
    )
    (comp (ref "R72")
      (value "220R 5%")
      (footprint "RES0603")
      (description "220±5%,1/10W,0603,国巨,RC0603JR-07220RL")
      (fields (field (name "PART NUMBER") "101010103-0019"))
      (libsource (lib "Database_Libs2") (part "RC03J_220R"))
    )
    (comp (ref "R73")
      (value "4.7K 5%")
      (footprint "RES0603")
      (description "4.7K±5%,1/10W,0603")
      (fields (field (name "PART NUMBER") "101010103-0042"))
      (libsource (lib "Database_Libs2") (part "RC03J_4.7K"))
    )
    (comp (ref "R74")
      (value "10K 5%")
      (footprint "RES0603")
      (description "国巨,±5%,0603,,155 ℃,-55 ℃,RC0603JR-0710KL,无铅,200 ppm/℃,1/10W,,10K")
      (fields (field (name "PART NUMBER") "101010103-0003"))
      (libsource (lib "Database_Libs2") (part "RC03J_10K"))
    )
    (comp (ref "R75")
      (value "10K 5%")
      (footprint "RES0603")
      (description "国巨,±5%,0603,,155 ℃,-55 ℃,RC0603JR-0710KL,无铅,200 ppm/℃,1/10W,,10K")
      (fields (field (name "PART NUMBER") "101010103-0003"))
      (libsource (lib "Database_Libs2") (part "RC03J_10K"))
    )
    (comp (ref "R76")
      (value "1K 5%")
      (footprint "RES0603")
      (description "1K,±5%,1/10W,0603,国巨,RC0603JR-071KL")
      (fields (field (name "PART NUMBER") "101010103-0008"))
      (libsource (lib "Database_Libs2") (part "RC03J_1K"))
    )
    (comp (ref "R77")
      (value "1K 5%")
      (footprint "RES0603")
      (description "1K,±5%,1/10W,0603,国巨,RC0603JR-071KL")
      (fields (field (name "PART NUMBER") "101010103-0008"))
      (libsource (lib "Database_Libs2") (part "RC03J_1K"))
    )
    (comp (ref "R78")
      (value "22R 5%")
      (footprint "RES0603")
      (description "国巨,±5%,0603,,155 ℃,-55 ℃,RC0603JR-0722RL,无铅,200 ppm/℃,1/10W,,22欧")
      (fields (field (name "PART NUMBER") "101010103-0009"))
      (libsource (lib "Database_Libs2") (part "RC03J_22R"))
    )
    (comp (ref "R79")
      (value "22R 5%")
      (footprint "RES0603")
      (description "国巨,±5%,0603,,155 ℃,-55 ℃,RC0603JR-0722RL,无铅,200 ppm/℃,1/10W,,22欧")
      (fields (field (name "PART NUMBER") "101010103-0009"))
      (libsource (lib "Database_Libs2") (part "RC03J_22R"))
    )
    (comp (ref "R80")
      (value "2M 5%")
      (footprint "RES0603")
      (description "国巨,±5%,0603,,155 ℃,-55 ℃,RC0603JR-072ML,含铅,100 ppm/℃,1/10W,,2M")
      (fields (field (name "PART NUMBER") "101010103-0025"))
      (libsource (lib "Database_Libs2") (part "RC03J_2M"))
    )
    (comp (ref "R81")
      (value "200K 5%")
      (footprint "RES0603")
      (description "200K,±5%,1/10W,0603,国巨,RC0603JR-07200KL")
      (fields (field (name "PART NUMBER") "101010103-0034"))
      (libsource (lib "Database_Libs2") (part "RC03J_200K"))
    )
    (comp (ref "R82")
      (value "1K 5%")
      (footprint "RES0603")
      (description "1K,±5%,1/10W,0603,国巨,RC0603JR-071KL")
      (fields (field (name "PART NUMBER") "101010103-0008"))
      (libsource (lib "Database_Libs2") (part "RC03J_1K"))
    )
    (comp (ref "U1") (value "ina219") (footprint "SO-8") (libsource (lib "Schlib1") (part "Component_2")))
    (comp (ref "U2")
      (value "TPS5430DDA")
      (footprint "SOP-8-P")
      (description "TPS5430DDA,SOP8,TI,TPS5430DDA")
      (fields (field (name "PART NUMBER") "101050101-0053"))
      (libsource (lib "Database_Libs2") (part "02_TPS5430DDA"))
    )
    (comp (ref "U3")
      (value "TPS5430DDA")
      (footprint "SOP-8-P")
      (description "TPS5430DDA,SOP8,TI,TPS5430DDA")
      (fields (field (name "PART NUMBER") "101050101-0053"))
      (libsource (lib "Database_Libs2") (part "02_TPS5430DDA"))
    )
    (comp (ref "U4")
      (value "TPS5430DDA")
      (footprint "SOP-8-P")
      (description "TPS5430DDA,SOP8,TI,TPS5430DDA")
      (fields (field (name "PART NUMBER") "101050101-0053"))
      (libsource (lib "Database_Libs2") (part "02_TPS5430DDA"))
    )
    (comp (ref "U5")
      (value "CE6232A33P")
      (footprint "SOT-89")
      (description "CE6232-3.3,CE6232-3.3,SOT89-3,8V,1.8V,0.11V,3.3V,300mA,0.8uA,南京芯力微电子有限公司")
      (fields (field (name "PART NUMBER") "1010503-0029"))
      (libsource (lib "Database_Libs2") (part "02_CE6232A33P"))
    )
    (comp (ref "U7") (value "ina219") (footprint "SO-8") (libsource (lib "Schlib1") (part "Component_2")))
  )
  (nets
    (net (code "1") (name "/3.6V_CHK") (class "Default")
      (node (ref "R38") (pin "1") (pinfunction "1_1") (pintype "passive"))
      (node (ref "R45") (pin "2") (pinfunction "2_2") (pintype "passive"))
    )
    (net (code "2") (name "/3.6V_CTL") (class "Default")
      (node (ref "R46") (pin "1") (pinfunction "1_1") (pintype "passive"))
    )
    (net (code "3") (name "/3.6V_I_CHK_CTR1") (class "Default")
      (node (ref "R14") (pin "2") (pinfunction "2_2") (pintype "passive"))
    )
    (net (code "4") (name "/3.6V_I_CHK_CTR2") (class "Default")
      (node (ref "R50") (pin "2") (pinfunction "2_2") (pintype "passive"))
    )
    (net (code "5") (name "/3.6V_Out") (class "Default")
      (node (ref "D6") (pin "2") (pinfunction "2_2") (pintype "passive"))
      (node (ref "Q5") (pin "2") (pinfunction "S_2") (pintype "passive"))
      (node (ref "R15") (pin "1") (pinfunction "1_1") (pintype "passive"))
      (node (ref "R22") (pin "2") (pinfunction "2_2") (pintype "passive"))
      (node (ref "R23") (pin "1") (pinfunction "1_1") (pintype "passive"))
    )
    (net (code "6") (name "/3.6V_Out1") (class "Default")
      (node (ref "J1") (pin "1") (pinfunction "1_1") (pintype "passive"))
      (node (ref "J1") (pin "3") (pinfunction "3_3") (pintype "passive"))
      (node (ref "Q5") (pin "3") (pinfunction "D_3") (pintype "passive"))
      (node (ref "R10") (pin "1") (pinfunction "1_1") (pintype "passive"))
      (node (ref "R15") (pin "2") (pinfunction "2_2") (pintype "passive"))
    )
    (net (code "7") (name "/12V_CHK") (class "Default")
      (node (ref "R26") (pin "1") (pinfunction "1_1") (pintype "passive"))
      (node (ref "R34") (pin "2") (pinfunction "2_2") (pintype "passive"))
    )
    (net (code "8") (name "/12V_CTL1") (class "Default")
      (node (ref "R69") (pin "1") (pinfunction "1_1") (pintype "passive"))
    )
    (net (code "9") (name "/12V_CTL2") (class "Default")
      (node (ref "R82") (pin "1") (pinfunction "1_1") (pintype "passive"))
    )
    (net (code "10") (name "/12V_Out1") (class "Default")
      (node (ref "D10") (pin "2") (pinfunction "2_2") (pintype "passive"))
      (node (ref "R35") (pin "1") (pinfunction "1_1") (pintype "passive"))
    )
    (net (code "11") (name "/12V_Out2") (class "Default")
      (node (ref "D4") (pin "2") (pinfunction "2_2") (pintype "passive"))
      (node (ref "R52") (pin "1") (pinfunction "1_1") (pintype "passive"))
    )
    (net (code "12") (name "/ADC_DRV+") (class "Default")
      (node (ref "R70") (pin "1") (pinfunction "1_1") (pintype "passive"))
      (node (ref "R75") (pin "2") (pinfunction "2_2") (pintype "passive"))
    )
    (net (code "13") (name "/ADC_DRV-") (class "Default")
      (node (ref "R71") (pin "1") (pinfunction "1_1") (pintype "passive"))
      (node (ref "R74") (pin "2") (pinfunction "2_2") (pintype "passive"))
    )
    (net (code "14") (name "/Analog_A") (class "Default")
      (node (ref "J1") (pin "6") (pinfunction "6_6") (pintype "passive"))
      (node (ref "P3") (pin "1") (pinfunction "1_1") (pintype "passive"))
    )
    (net (code "15") (name "/Analog_B") (class "Default")
      (node (ref "J1") (pin "8") (pinfunction "8_8") (pintype "passive"))
      (node (ref "P3") (pin "2") (pinfunction "2_2") (pintype "passive"))
    )
    (net (code "16") (name "/CLOSE") (class "Default")
      (node (ref "R40") (pin "1") (pinfunction "1_1") (pintype "passive"))
    )
    (net (code "17") (name "/DRV+") (class "Default")
      (node (ref "J1") (pin "12") (pinfunction "12_12") (pintype "passive"))
      (node (ref "R70") (pin "2") (pinfunction "2_2") (pintype "passive"))
    )
    (net (code "18") (name "/DRV-") (class "Default")
      (node (ref "J1") (pin "10") (pinfunction "10_10") (pintype "passive"))
      (node (ref "R71") (pin "2") (pinfunction "2_2") (pintype "passive"))
    )
    (net (code "19") (name "/Ext_VCC") (class "Default")
      (node (ref "J1") (pin "7") (pinfunction "7_7") (pintype "passive"))
      (node (ref "Q1") (pin "2") (pinfunction "E_2") (pintype "passive"))
      (node (ref "R4") (pin "2") (pinfunction "2_2") (pintype "passive"))
    )
    (net (code "20") (name "/Ext_VCC_CHK") (class "Default")
      (node (ref "R16") (pin "1") (pinfunction "1_1") (pintype "passive"))
      (node (ref "R6") (pin "2") (pinfunction "2_2") (pintype "passive"))
    )
    (net (code "21") (name "/Ext_VCC_CHK_CTR") (class "Default")
      (node (ref "R19") (pin "1") (pinfunction "1_1") (pintype "passive"))
    )
    (net (code "22") (name "/FM_RXD") (class "Default")
      (node (ref "R77") (pin "1") (pinfunction "1_1") (pintype "passive"))
    )
    (net (code "23") (name "/FM_TXD") (class "Default")
      (node (ref "R76") (pin "1") (pinfunction "1_1") (pintype "passive"))
    )
    (net (code "24") (name "/INA1_SCL") (class "Default")
      (node (ref "R2") (pin "2") (pinfunction "2_2") (pintype "passive"))
      (node (ref "U1") (pin "4") (pinfunction "SCL_4") (pintype "passive"))
    )
    (net (code "25") (name "/INA1_SDA") (class "Default")
      (node (ref "R3") (pin "2") (pinfunction "2_2") (pintype "passive"))
      (node (ref "U1") (pin "3") (pinfunction "SDA_3") (pintype "passive"))
    )
    (net (code "26") (name "/INA2_SCL") (class "Default")
      (node (ref "R28") (pin "2") (pinfunction "2_2") (pintype "passive"))
      (node (ref "U7") (pin "4") (pinfunction "SCL_4") (pintype "passive"))
    )
    (net (code "27") (name "/INA2_SDA") (class "Default")
      (node (ref "R32") (pin "2") (pinfunction "2_2") (pintype "passive"))
      (node (ref "U7") (pin "3") (pinfunction "SDA_3") (pintype "passive"))
    )
    (net (code "28") (name "/IO1") (class "Default")
      (node (ref "J1") (pin "15") (pinfunction "15_15") (pintype "passive"))
    )
    (net (code "29") (name "/IO2") (class "Default")
      (node (ref "J1") (pin "20") (pinfunction "20_20") (pintype "passive"))
    )
    (net (code "30") (name "/IR_R") (class "Default")
      (node (ref "C2") (pin "1") (pinfunction "1_1") (pintype "passive"))
      (node (ref "Q8") (pin "3") (pinfunction "C_3") (pintype "passive"))
      (node (ref "R1") (pin "2") (pinfunction "2_2") (pintype "passive"))
      (node (ref "R27") (pin "2") (pinfunction "2_2") (pintype "passive"))
    )
    (net (code "31") (name "/IR_RXD") (class "Default")
      (node (ref "P2") (pin "2") (pinfunction "2_2") (pintype "passive"))
      (node (ref "R27") (pin "1") (pinfunction "1_1") (pintype "passive"))
    )
    (net (code "32") (name "/IR_T") (class "Default")
      (node (ref "R11") (pin "1") (pinfunction "1_1") (pintype "passive"))
      (node (ref "R17") (pin "1") (pinfunction "1_1") (pintype "passive"))
      (node (ref "R25") (pin "2") (pinfunction "2_2") (pintype "passive"))
    )
    (net (code "33") (name "/IR_TXD") (class "Default")
      (node (ref "P2") (pin "3") (pinfunction "3_3") (pintype "passive"))
      (node (ref "R25") (pin "1") (pinfunction "1_1") (pintype "passive"))
    )
    (net (code "34") (name "/MCU_RXD") (class "Default")
      (node (ref "R48") (pin "1") (pinfunction "1_1") (pintype "passive"))
    )
    (net (code "35") (name "/MCU_TXD") (class "Default")
      (node (ref "R47") (pin "1") (pinfunction "1_1") (pintype "passive"))
    )
    (net (code "36") (name "/OPEN") (class "Default")
      (node (ref "R41") (pin "1") (pinfunction "1_1") (pintype "passive"))
    )
    (net (code "37") (name "/PC_RXD") (class "Default")
      (node (ref "P5") (pin "2") (pinfunction "2_2") (pintype "passive"))
      (node (ref "R76") (pin "2") (pinfunction "2_2") (pintype "passive"))
      (node (ref "R78") (pin "1") (pinfunction "1_1") (pintype "passive"))
    )
    (net (code "38") (name "/PC_TXD") (class "Default")
      (node (ref "P5") (pin "3") (pinfunction "3_3") (pintype "passive"))
      (node (ref "R77") (pin "2") (pinfunction "2_2") (pintype "passive"))
      (node (ref "R79") (pin "1") (pinfunction "1_1") (pintype "passive"))
    )
    (net (code "39") (name "/RF_NB_CTL") (class "Default")
      (node (ref "R53") (pin "1") (pinfunction "1_1") (pintype "passive"))
    )
    (net (code "40") (name "/RF_NB_GD") (class "Default")
      (node (ref "D3") (pin "2") (pinfunction "2_2") (pintype "passive"))
      (node (ref "Q11") (pin "2") (pinfunction "S_2") (pintype "passive"))
      (node (ref "R51") (pin "1") (pinfunction "1_1") (pintype "passive"))
      (node (ref "R54") (pin "2") (pinfunction "2_2") (pintype "passive"))
      (node (ref "R55") (pin "1") (pinfunction "1_1") (pintype "passive"))
    )
    (net (code "41") (name "/RF_NB_GD1") (class "Default")
      (node (ref "J1") (pin "5") (pinfunction "5_5") (pintype "passive"))
      (node (ref "Q11") (pin "3") (pinfunction "D_3") (pintype "passive"))
      (node (ref "R36") (pin "1") (pinfunction "1_1") (pintype "passive"))
      (node (ref "R51") (pin "2") (pinfunction "2_2") (pintype "passive"))
    )
    (net (code "42") (name "/RXD") (class "Default")
      (node (ref "J1") (pin "19") (pinfunction "19_19") (pintype "passive"))
      (node (ref "R48") (pin "2") (pinfunction "2_2") (pintype "passive"))
    )
    (net (code "43") (name "/Simulate_RXD") (class "Default")
      (node (ref "R61") (pin "1") (pinfunction "1_1") (pintype "passive"))
    )
    (net (code "44") (name "/Simulate_TXD") (class "Default")
      (node (ref "R62") (pin "1") (pinfunction "1_1") (pintype "passive"))
    )
    (net (code "45") (name "/TXD") (class "Default")
      (node (ref "J1") (pin "17") (pinfunction "17_17") (pintype "passive"))
      (node (ref "R47") (pin "2") (pinfunction "2_2") (pintype "passive"))
    )
    (net (code "46") (name "/VCC_RF_NB") (class "Default")
      (node (ref "J1") (pin "9") (pinfunction "9_9") (pintype "passive"))
      (node (ref "Q2") (pin "2") (pinfunction "E_2") (pintype "passive"))
      (node (ref "R5") (pin "2") (pinfunction "2_2") (pintype "passive"))
    )
    (net (code "47") (name "/VCC_RF_NB_CHK") (class "Default")
      (node (ref "R18") (pin "1") (pinfunction "1_1") (pintype "passive"))
      (node (ref "R7") (pin "2") (pinfunction "2_2") (pintype "passive"))
    )
    (net (code "48") (name "/VCC_RF_NB_CHK_CTR") (class "Default")
      (node (ref "R20") (pin "1") (pinfunction "1_1") (pintype "passive"))
    )
    (net (code "49") (name "/VIN_5V_CHK") (class "Default")
      (node (ref "R56") (pin "1") (pinfunction "1_1") (pintype "passive"))
      (node (ref "R60") (pin "2") (pinfunction "2_2") (pintype "passive"))
    )
    (net (code "50") (name "/WF7502_D") (class "Default")
      (node (ref "J1") (pin "18") (pinfunction "18_18") (pintype "passive"))
    )
    (net (code "51") (name "/WF7502_P") (class "Default")
      (node (ref "J1") (pin "16") (pinfunction "16_16") (pintype "passive"))
    )
    (net (code "52") (name "/WF7502_T") (class "Default")
      (node (ref "J1") (pin "14") (pinfunction "14_14") (pintype "passive"))
      (node (ref "R49") (pin "2") (pinfunction "2_2") (pintype "passive"))
    )
    (net (code "53") (name "/WF7502_TXD") (class "Default")
      (node (ref "R49") (pin "1") (pinfunction "1_1") (pintype "passive"))
    )
    (net (code "54") (name "3.3V") (class "Default")
      (node (ref "C1") (pin "2") (pinfunction "2_2") (pintype "passive"))
      (node (ref "C15") (pin "1") (pinfunction "1_1") (pintype "passive"))
      (node (ref "C17") (pin "1") (pinfunction "1_1") (pintype "passive"))
      (node (ref "C18") (pin "1") (pinfunction "1_1") (pintype "passive"))
      (node (ref "C24") (pin "2") (pinfunction "2_2") (pintype "passive"))
      (node (ref "D1") (pin "1") (pinfunction "1_1") (pintype "passive"))
      (node (ref "D2") (pin "2") (pinfunction "K_2") (pintype "passive"))
      (node (ref "JP4") (pin "1") (pinfunction "1_1") (pintype "passive"))
      (node (ref "P1") (pin "1") (pinfunction "1_1") (pintype "passive"))
      (node (ref "P1") (pin "4") (pinfunction "4_4") (pintype "passive"))
      (node (ref "P2") (pin "4") (pinfunction "4_4") (pintype "passive"))
      (node (ref "P4") (pin "1") (pinfunction "1_1") (pintype "passive"))
      (node (ref "R1") (pin "1") (pinfunction "1_1") (pintype "passive"))
      (node (ref "R11") (pin "2") (pinfunction "2_2") (pintype "passive"))
      (node (ref "R2") (pin "1") (pinfunction "1_1") (pintype "passive"))
      (node (ref "R28") (pin "1") (pinfunction "1_1") (pintype "passive"))
      (node (ref "R3") (pin "1") (pinfunction "1_1") (pintype "passive"))
      (node (ref "R32") (pin "1") (pinfunction "1_1") (pintype "passive"))
      (node (ref "U1") (pin "5") (pinfunction "Vs_5") (pintype "passive"))
      (node (ref "U5") (pin "3") (pinfunction "Vout_3") (pintype "passive"))
      (node (ref "U7") (pin "5") (pinfunction "Vs_5") (pintype "passive"))
    )
    (net (code "55") (name "3.6V") (class "Default")
      (node (ref "C10") (pin "1") (pinfunction "1_1") (pintype "passive"))
      (node (ref "L2") (pin "2") (pinfunction "2_2") (pintype "passive"))
      (node (ref "Q13") (pin "2") (pinfunction "S_2") (pintype "passive"))
      (node (ref "Q9") (pin "2") (pinfunction "S_2") (pintype "passive"))
      (node (ref "R33") (pin "1") (pinfunction "1_1") (pintype "passive"))
      (node (ref "R38") (pin "2") (pinfunction "2_2") (pintype "passive"))
      (node (ref "R39") (pin "1") (pinfunction "1_1") (pintype "passive"))
      (node (ref "R43") (pin "2") (pinfunction "2_2") (pintype "passive"))
    )
    (net (code "56") (name "12V") (class "Default")
      (node (ref "C7") (pin "1") (pinfunction "1_1") (pintype "passive"))
      (node (ref "L1") (pin "2") (pinfunction "2_2") (pintype "passive"))
      (node (ref "Q15") (pin "2") (pinfunction "S_2") (pintype "passive"))
      (node (ref "Q17") (pin "2") (pinfunction "S_2") (pintype "passive"))
      (node (ref "R26") (pin "2") (pinfunction "2_2") (pintype "passive"))
      (node (ref "R31") (pin "2") (pinfunction "2_2") (pintype "passive"))
      (node (ref "R67") (pin "1") (pinfunction "1_1") (pintype "passive"))
      (node (ref "R80") (pin "1") (pinfunction "1_1") (pintype "passive"))
    )
    (net (code "57") (name "GND") (class "Default")
      (node (ref "C1") (pin "1") (pinfunction "1_1") (pintype "passive"))
      (node (ref "C10") (pin "2") (pinfunction "2_2") (pintype "passive"))
      (node (ref "C12") (pin "2") (pinfunction "2_2") (pintype "passive"))
      (node (ref "C13") (pin "2") (pinfunction "2_2") (pintype "passive"))
      (node (ref "C14") (pin "2") (pinfunction "2_2") (pintype "passive"))
      (node (ref "C15") (pin "2") (pinfunction "2_2") (pintype "passive"))
      (node (ref "C16") (pin "2") (pinfunction "2_2") (pintype "passive"))
      (node (ref "C17") (pin "2") (pinfunction "2_2") (pintype "passive"))
      (node (ref "C18") (pin "2") (pinfunction "2_2") (pintype "passive"))
      (node (ref "C2") (pin "2") (pinfunction "2_2") (pintype "passive"))
      (node (ref "C24") (pin "1") (pinfunction "1_1") (pintype "passive"))
      (node (ref "C4") (pin "2") (pinfunction "2_2") (pintype "passive"))
      (node (ref "C6") (pin "2") (pinfunction "2_2") (pintype "passive"))
      (node (ref "C7") (pin "2") (pinfunction "2_2") (pintype "passive"))
      (node (ref "C9") (pin "2") (pinfunction "2_2") (pintype "passive"))
      (node (ref "D5") (pin "1") (pinfunction "1_1") (pintype "passive"))
      (node (ref "D7") (pin "1") (pinfunction "1_1") (pintype "passive"))
      (node (ref "D8") (pin "1") (pinfunction "1_1") (pintype "passive"))
      (node (ref "J1") (pin "2") (pinfunction "2_2") (pintype "passive"))
      (node (ref "J1") (pin "4") (pinfunction "4_4") (pintype "passive"))
      (node (ref "JP1") (pin "2") (pinfunction "2_2") (pintype "passive"))
      (node (ref "JP2") (pin "2") (pinfunction "2_2") (pintype "passive"))
      (node (ref "JP3") (pin "2") (pinfunction "2_2") (pintype "passive"))
      (node (ref "JP4") (pin "2") (pinfunction "2_2") (pintype "passive"))
      (node (ref "JP5") (pin "2") (pinfunction "2_2") (pintype "passive"))
      (node (ref "P2") (pin "1") (pinfunction "1_1") (pintype "passive"))
      (node (ref "P3") (pin "3") (pinfunction "3_3") (pintype "passive"))
      (node (ref "P4") (pin "4") (pinfunction "4_4") (pintype "passive"))
      (node (ref "P5") (pin "4") (pinfunction "4_4") (pintype "passive"))
      (node (ref "P6") (pin "4") (pinfunction "4_4") (pintype "passive"))
      (node (ref "Q10") (pin "2") (pinfunction "E_2") (pintype "passive"))
      (node (ref "Q12") (pin "2") (pinfunction "E_2") (pintype "passive"))
      (node (ref "Q14") (pin "2") (pinfunction "E_2") (pintype "passive"))
      (node (ref "Q16") (pin "2") (pinfunction "E_2") (pintype "passive"))
      (node (ref "Q18") (pin "2") (pinfunction "E_2") (pintype "passive"))
      (node (ref "Q3") (pin "3") (pinfunction "C_3") (pintype "passive"))
      (node (ref "Q4") (pin "2") (pinfunction "E_2") (pintype "passive"))
      (node (ref "Q6") (pin "2") (pinfunction "E_2") (pintype "passive"))
      (node (ref "Q7") (pin "2") (pinfunction "E_2") (pintype "passive"))
      (node (ref "Q8") (pin "2") (pinfunction "E_2") (pintype "passive"))
      (node (ref "R16") (pin "2") (pinfunction "2_2") (pintype "passive"))
      (node (ref "R18") (pin "2") (pinfunction "2_2") (pintype "passive"))
      (node (ref "R24") (pin "1") (pinfunction "1_1") (pintype "passive"))
      (node (ref "R29") (pin "1") (pinfunction "1_1") (pintype "passive"))
      (node (ref "R34") (pin "1") (pinfunction "1_1") (pintype "passive"))
      (node (ref "R45") (pin "1") (pinfunction "1_1") (pintype "passive"))
      (node (ref "R57") (pin "1") (pinfunction "1_1") (pintype "passive"))
      (node (ref "R60") (pin "1") (pinfunction "1_1") (pintype "passive"))
      (node (ref "R72") (pin "1") (pinfunction "1_1") (pintype "passive"))
      (node (ref "R74") (pin "1") (pinfunction "1_1") (pintype "passive"))
      (node (ref "R75") (pin "1") (pinfunction "1_1") (pintype "passive"))
      (node (ref "U1") (pin "1") (pinfunction "A1_1") (pintype "passive"))
      (node (ref "U1") (pin "2") (pinfunction "A0_2") (pintype "passive"))
      (node (ref "U1") (pin "6") (pinfunction "GND_6") (pintype "passive"))
      (node (ref "U2") (pin "6") (pinfunction "GND_6") (pintype "passive"))
      (node (ref "U2") (pin "9") (pinfunction "PAD_9") (pintype "passive"))
      (node (ref "U3") (pin "6") (pinfunction "GND_6") (pintype "passive"))
      (node (ref "U3") (pin "9") (pinfunction "PAD_9") (pintype "passive"))
      (node (ref "U4") (pin "6") (pinfunction "GND_6") (pintype "passive"))
      (node (ref "U4") (pin "9") (pinfunction "PAD_9") (pintype "passive"))
      (node (ref "U5") (pin "1") (pinfunction "GND_1") (pintype "passive"))
      (node (ref "U7") (pin "1") (pinfunction "A1_1") (pintype "passive"))
      (node (ref "U7") (pin "2") (pinfunction "A0_2") (pintype "passive"))
      (node (ref "U7") (pin "6") (pinfunction "GND_6") (pintype "passive"))
    )
    (net (code "58") (name "Net-(D1-Pad2)") (class "Default")
      (node (ref "D1") (pin "2") (pinfunction "2_2") (pintype "passive"))
      (node (ref "P1") (pin "2") (pinfunction "2_2") (pintype "passive"))
      (node (ref "R8") (pin "2") (pinfunction "2_2") (pintype "passive"))
    )
    (net (code "59") (name "Net-(D2-A)") (class "Default")
      (node (ref "D2") (pin "1") (pinfunction "A_1") (pintype "passive"))
      (node (ref "P1") (pin "3") (pinfunction "3_3") (pintype "passive"))
      (node (ref "R21") (pin "2") (pinfunction "2_2") (pintype "passive"))
    )
    (net (code "60") (name "Net-(J1-Pad11)") (class "Default")
      (node (ref "J1") (pin "11") (pinfunction "11_11") (pintype "passive"))
      (node (ref "R40") (pin "2") (pinfunction "2_2") (pintype "passive"))
    )
    (net (code "61") (name "Net-(J1-Pad13)") (class "Default")
      (node (ref "J1") (pin "13") (pinfunction "13_13") (pintype "passive"))
      (node (ref "R41") (pin "2") (pinfunction "2_2") (pintype "passive"))
    )
    (net (code "62") (name "Net-(JP1-Pad1)") (class "Default")
      (node (ref "JP1") (pin "1") (pinfunction "1_1") (pintype "passive"))
      (node (ref "R35") (pin "2") (pinfunction "2_2") (pintype "passive"))
    )
    (net (code "63") (name "Net-(JP5-Pad1)") (class "Default")
      (node (ref "JP5") (pin "1") (pinfunction "1_1") (pintype "passive"))
      (node (ref "R52") (pin "2") (pinfunction "2_2") (pintype "passive"))
    )
    (net (code "64") (name "Net-(P4-Pad2)") (class "Default")
      (node (ref "P4") (pin "2") (pinfunction "2_2") (pintype "passive"))
      (node (ref "R61") (pin "2") (pinfunction "2_2") (pintype "passive"))
    )
    (net (code "65") (name "Net-(P4-Pad3)") (class "Default")
      (node (ref "P4") (pin "3") (pinfunction "3_3") (pintype "passive"))
      (node (ref "R62") (pin "2") (pinfunction "2_2") (pintype "passive"))
    )
    (net (code "66") (name "Net-(P6-Pad2)") (class "Default")
      (node (ref "P6") (pin "2") (pinfunction "2_2") (pintype "passive"))
      (node (ref "R78") (pin "2") (pinfunction "2_2") (pintype "passive"))
    )
    (net (code "67") (name "Net-(P6-Pad3)") (class "Default")
      (node (ref "P6") (pin "3") (pinfunction "3_3") (pintype "passive"))
      (node (ref "R79") (pin "2") (pinfunction "2_2") (pintype "passive"))
    )
    (net (code "68") (name "Net-(Q1-B)") (class "Default")
      (node (ref "Q1") (pin "1") (pinfunction "B_1") (pintype "passive"))
      (node (ref "R4") (pin "1") (pinfunction "1_1") (pintype "passive"))
      (node (ref "R9") (pin "1") (pinfunction "1_1") (pintype "passive"))
    )
    (net (code "69") (name "Net-(Q1-C)") (class "Default")
      (node (ref "Q1") (pin "3") (pinfunction "C_3") (pintype "passive"))
      (node (ref "R6") (pin "1") (pinfunction "1_1") (pintype "passive"))
    )
    (net (code "70") (name "Net-(Q2-B)") (class "Default")
      (node (ref "Q2") (pin "1") (pinfunction "B_1") (pintype "passive"))
      (node (ref "R12") (pin "1") (pinfunction "1_1") (pintype "passive"))
      (node (ref "R5") (pin "1") (pinfunction "1_1") (pintype "passive"))
    )
    (net (code "71") (name "Net-(Q2-C)") (class "Default")
      (node (ref "Q2") (pin "3") (pinfunction "C_3") (pintype "passive"))
      (node (ref "R7") (pin "1") (pinfunction "1_1") (pintype "passive"))
    )
    (net (code "72") (name "Net-(Q3-B)") (class "Default")
      (node (ref "Q3") (pin "1") (pinfunction "B_1") (pintype "passive"))
      (node (ref "R17") (pin "2") (pinfunction "2_2") (pintype "passive"))
    )
    (net (code "73") (name "Net-(Q3-E)") (class "Default")
      (node (ref "Q3") (pin "2") (pinfunction "E_2") (pintype "passive"))
      (node (ref "R8") (pin "1") (pinfunction "1_1") (pintype "passive"))
    )
    (net (code "74") (name "Net-(Q4-B)") (class "Default")
      (node (ref "Q4") (pin "1") (pinfunction "B_1") (pintype "passive"))
      (node (ref "R14") (pin "1") (pinfunction "1_1") (pintype "passive"))
    )
    (net (code "75") (name "Net-(Q4-C)") (class "Default")
      (node (ref "Q4") (pin "3") (pinfunction "C_3") (pintype "passive"))
      (node (ref "R13") (pin "2") (pinfunction "2_2") (pintype "passive"))
    )
    (net (code "76") (name "Net-(Q5-G)") (class "Default")
      (node (ref "Q5") (pin "1") (pinfunction "G_1") (pintype "passive"))
      (node (ref "R13") (pin "1") (pinfunction "1_1") (pintype "passive"))
      (node (ref "R22") (pin "1") (pinfunction "1_1") (pintype "passive"))
    )
    (net (code "77") (name "Net-(Q6-B)") (class "Default")
      (node (ref "Q6") (pin "1") (pinfunction "B_1") (pintype "passive"))
      (node (ref "R19") (pin "2") (pinfunction "2_2") (pintype "passive"))
    )
    (net (code "78") (name "Net-(Q6-C)") (class "Default")
      (node (ref "Q6") (pin "3") (pinfunction "C_3") (pintype "passive"))
      (node (ref "R9") (pin "2") (pinfunction "2_2") (pintype "passive"))
    )
    (net (code "79") (name "Net-(Q7-B)") (class "Default")
      (node (ref "Q7") (pin "1") (pinfunction "B_1") (pintype "passive"))
      (node (ref "R20") (pin "2") (pinfunction "2_2") (pintype "passive"))
    )
    (net (code "80") (name "Net-(Q7-C)") (class "Default")
      (node (ref "Q7") (pin "3") (pinfunction "C_3") (pintype "passive"))
      (node (ref "R12") (pin "2") (pinfunction "2_2") (pintype "passive"))
    )
    (net (code "81") (name "Net-(Q8-B)") (class "Default")
      (node (ref "C4") (pin "1") (pinfunction "1_1") (pintype "passive"))
      (node (ref "Q8") (pin "1") (pinfunction "B_1") (pintype "passive"))
      (node (ref "R21") (pin "1") (pinfunction "1_1") (pintype "passive"))
      (node (ref "R24") (pin "2") (pinfunction "2_2") (pintype "passive"))
    )
    (net (code "82") (name "Net-(Q9-D)") (class "Default")
      (node (ref "D3") (pin "1") (pinfunction "1_1") (pintype "passive"))
      (node (ref "Q9") (pin "3") (pinfunction "D_3") (pintype "passive"))
    )
    (net (code "83") (name "Net-(Q9-G)") (class "Default")
      (node (ref "Q9") (pin "1") (pinfunction "G_1") (pintype "passive"))
      (node (ref "R33") (pin "2") (pinfunction "2_2") (pintype "passive"))
      (node (ref "R42") (pin "2") (pinfunction "2_2") (pintype "passive"))
    )
    (net (code "84") (name "Net-(Q10-B)") (class "Default")
      (node (ref "Q10") (pin "1") (pinfunction "B_1") (pintype "passive"))
      (node (ref "R50") (pin "1") (pinfunction "1_1") (pintype "passive"))
    )
    (net (code "85") (name "Net-(Q10-C)") (class "Default")
      (node (ref "Q10") (pin "3") (pinfunction "C_3") (pintype "passive"))
      (node (ref "R37") (pin "2") (pinfunction "2_2") (pintype "passive"))
    )
    (net (code "86") (name "Net-(Q11-G)") (class "Default")
      (node (ref "Q11") (pin "1") (pinfunction "G_1") (pintype "passive"))
      (node (ref "R37") (pin "1") (pinfunction "1_1") (pintype "passive"))
      (node (ref "R54") (pin "1") (pinfunction "1_1") (pintype "passive"))
    )
    (net (code "87") (name "Net-(Q12-B)") (class "Default")
      (node (ref "Q12") (pin "1") (pinfunction "B_1") (pintype "passive"))
      (node (ref "R53") (pin "2") (pinfunction "2_2") (pintype "passive"))
    )
    (net (code "88") (name "Net-(Q12-C)") (class "Default")
      (node (ref "Q12") (pin "3") (pinfunction "C_3") (pintype "passive"))
      (node (ref "R42") (pin "1") (pinfunction "1_1") (pintype "passive"))
    )
    (net (code "89") (name "Net-(Q13-D)") (class "Default")
      (node (ref "D6") (pin "1") (pinfunction "1_1") (pintype "passive"))
      (node (ref "Q13") (pin "3") (pinfunction "D_3") (pintype "passive"))
    )
    (net (code "90") (name "Net-(Q13-G)") (class "Default")
      (node (ref "Q13") (pin "1") (pinfunction "G_1") (pintype "passive"))
      (node (ref "R39") (pin "2") (pinfunction "2_2") (pintype "passive"))
      (node (ref "R44") (pin "2") (pinfunction "2_2") (pintype "passive"))
    )
    (net (code "91") (name "Net-(Q14-B)") (class "Default")
      (node (ref "Q14") (pin "1") (pinfunction "B_1") (pintype "passive"))
      (node (ref "R46") (pin "2") (pinfunction "2_2") (pintype "passive"))
    )
    (net (code "92") (name "Net-(Q14-C)") (class "Default")
      (node (ref "Q14") (pin "3") (pinfunction "C_3") (pintype "passive"))
      (node (ref "R44") (pin "1") (pinfunction "1_1") (pintype "passive"))
    )
    (net (code "93") (name "Net-(Q15-D)") (class "Default")
      (node (ref "D10") (pin "1") (pinfunction "1_1") (pintype "passive"))
      (node (ref "Q15") (pin "3") (pinfunction "D_3") (pintype "passive"))
    )
    (net (code "94") (name "Net-(Q15-G)") (class "Default")
      (node (ref "Q15") (pin "1") (pinfunction "G_1") (pintype "passive"))
      (node (ref "R67") (pin "2") (pinfunction "2_2") (pintype "passive"))
      (node (ref "R68") (pin "2") (pinfunction "2_2") (pintype "passive"))
    )
    (net (code "95") (name "Net-(Q16-B)") (class "Default")
      (node (ref "Q16") (pin "1") (pinfunction "B_1") (pintype "passive"))
      (node (ref "R69") (pin "2") (pinfunction "2_2") (pintype "passive"))
    )
    (net (code "96") (name "Net-(Q16-C)") (class "Default")
      (node (ref "Q16") (pin "3") (pinfunction "C_3") (pintype "passive"))
      (node (ref "R68") (pin "1") (pinfunction "1_1") (pintype "passive"))
    )
    (net (code "97") (name "Net-(Q17-D)") (class "Default")
      (node (ref "D4") (pin "1") (pinfunction "1_1") (pintype "passive"))
      (node (ref "Q17") (pin "3") (pinfunction "D_3") (pintype "passive"))
    )
    (net (code "98") (name "Net-(Q17-G)") (class "Default")
      (node (ref "Q17") (pin "1") (pinfunction "G_1") (pintype "passive"))
      (node (ref "R80") (pin "2") (pinfunction "2_2") (pintype "passive"))
      (node (ref "R81") (pin "2") (pinfunction "2_2") (pintype "passive"))
    )
    (net (code "99") (name "Net-(Q18-B)") (class "Default")
      (node (ref "Q18") (pin "1") (pinfunction "B_1") (pintype "passive"))
      (node (ref "R82") (pin "2") (pinfunction "2_2") (pintype "passive"))
    )
    (net (code "100") (name "Net-(Q18-C)") (class "Default")
      (node (ref "Q18") (pin "3") (pinfunction "C_3") (pintype "passive"))
      (node (ref "R81") (pin "1") (pinfunction "1_1") (pintype "passive"))
    )
    (net (code "101") (name "Net-(R29-Pad2)") (class "Default")
      (node (ref "R29") (pin "2") (pinfunction "2_2") (pintype "passive"))
      (node (ref "R30") (pin "1") (pinfunction "1_1") (pintype "passive"))
    )
    (net (code "102") (name "Net-(R57-Pad2)") (class "Default")
      (node (ref "R57") (pin "2") (pinfunction "2_2") (pintype "passive"))
      (node (ref "R58") (pin "1") (pinfunction "1_1") (pintype "passive"))
    )
    (net (code "103") (name "Net-(R72-Pad2)") (class "Default")
      (node (ref "R72") (pin "2") (pinfunction "2_2") (pintype "passive"))
      (node (ref "R73") (pin "1") (pinfunction "1_1") (pintype "passive"))
    )
    (net (code "104") (name "Net-(U1-Vin+)") (class "Default")
      (node (ref "C3") (pin "2") (pinfunction "2_2") (pintype "passive"))
      (node (ref "R23") (pin "2") (pinfunction "2_2") (pintype "passive"))
      (node (ref "U1") (pin "8") (pinfunction "Vin+_8") (pintype "passive"))
    )
    (net (code "105") (name "Net-(U1-Vin-)") (class "Default")
      (node (ref "C3") (pin "1") (pinfunction "1_1") (pintype "passive"))
      (node (ref "R10") (pin "2") (pinfunction "2_2") (pintype "passive"))
      (node (ref "U1") (pin "7") (pinfunction "Vin-_7") (pintype "passive"))
    )
    (net (code "106") (name "Net-(U2-BOOT)") (class "Default")
      (node (ref "C5") (pin "2") (pinfunction "2_2") (pintype "passive"))
      (node (ref "U2") (pin "1") (pinfunction "BOOT_1") (pintype "passive"))
    )
    (net (code "107") (name "Net-(U2-PH)") (class "Default")
      (node (ref "C5") (pin "1") (pinfunction "1_1") (pintype "passive"))
      (node (ref "D5") (pin "2") (pinfunction "2_2") (pintype "passive"))
      (node (ref "L1") (pin "1") (pinfunction "1_1") (pintype "passive"))
      (node (ref "U2") (pin "8") (pinfunction "PH_8") (pintype "passive"))
    )
    (net (code "108") (name "Net-(U2-VSNS)") (class "Default")
      (node (ref "R30") (pin "2") (pinfunction "2_2") (pintype "passive"))
      (node (ref "R31") (pin "1") (pinfunction "1_1") (pintype "passive"))
      (node (ref "U2") (pin "4") (pinfunction "VSNS_4") (pintype "passive"))
    )
    (net (code "109") (name "Net-(U3-BOOT)") (class "Default")
      (node (ref "C8") (pin "2") (pinfunction "2_2") (pintype "passive"))
      (node (ref "U3") (pin "1") (pinfunction "BOOT_1") (pintype "passive"))
    )
    (net (code "110") (name "Net-(U3-PH)") (class "Default")
      (node (ref "C8") (pin "1") (pinfunction "1_1") (pintype "passive"))
      (node (ref "D7") (pin "2") (pinfunction "2_2") (pintype "passive"))
      (node (ref "L2") (pin "1") (pinfunction "1_1") (pintype "passive"))
      (node (ref "U3") (pin "8") (pinfunction "PH_8") (pintype "passive"))
    )
    (net (code "111") (name "Net-(U3-VSNS)") (class "Default")
      (node (ref "R43") (pin "1") (pinfunction "1_1") (pintype "passive"))
      (node (ref "R73") (pin "2") (pinfunction "2_2") (pintype "passive"))
      (node (ref "U3") (pin "4") (pinfunction "VSNS_4") (pintype "passive"))
    )
    (net (code "112") (name "Net-(U4-BOOT)") (class "Default")
      (node (ref "C11") (pin "2") (pinfunction "2_2") (pintype "passive"))
      (node (ref "U4") (pin "1") (pinfunction "BOOT_1") (pintype "passive"))
    )
    (net (code "113") (name "Net-(U4-PH)") (class "Default")
      (node (ref "C11") (pin "1") (pinfunction "1_1") (pintype "passive"))
      (node (ref "D8") (pin "2") (pinfunction "2_2") (pintype "passive"))
      (node (ref "L3") (pin "1") (pinfunction "1_1") (pintype "passive"))
      (node (ref "U4") (pin "8") (pinfunction "PH_8") (pintype "passive"))
    )
    (net (code "114") (name "Net-(U4-VSNS)") (class "Default")
      (node (ref "R58") (pin "2") (pinfunction "2_2") (pintype "passive"))
      (node (ref "R59") (pin "2") (pinfunction "2_2") (pintype "passive"))
      (node (ref "U4") (pin "4") (pinfunction "VSNS_4") (pintype "passive"))
    )
    (net (code "115") (name "Net-(U7-Vin+)") (class "Default")
      (node (ref "C25") (pin "2") (pinfunction "2_2") (pintype "passive"))
      (node (ref "R55") (pin "2") (pinfunction "2_2") (pintype "passive"))
      (node (ref "U7") (pin "8") (pinfunction "Vin+_8") (pintype "passive"))
    )
    (net (code "116") (name "Net-(U7-Vin-)") (class "Default")
      (node (ref "C25") (pin "1") (pinfunction "1_1") (pintype "passive"))
      (node (ref "R36") (pin "2") (pinfunction "2_2") (pintype "passive"))
      (node (ref "U7") (pin "7") (pinfunction "Vin-_7") (pintype "passive"))
    )
    (net (code "117") (name "VIN_5V") (class "Default")
      (node (ref "C14") (pin "1") (pinfunction "1_1") (pintype "passive"))
      (node (ref "C16") (pin "1") (pinfunction "1_1") (pintype "passive"))
      (node (ref "L3") (pin "2") (pinfunction "2_2") (pintype "passive"))
      (node (ref "R56") (pin "2") (pinfunction "2_2") (pintype "passive"))
      (node (ref "R59") (pin "1") (pinfunction "1_1") (pintype "passive"))
      (node (ref "U5") (pin "2") (pinfunction "Vin_2") (pintype "passive"))
    )
    (net (code "118") (name "VIN_24V") (class "Default")
      (node (ref "C12") (pin "1") (pinfunction "1_1") (pintype "passive"))
      (node (ref "C13") (pin "1") (pinfunction "1_1") (pintype "passive"))
      (node (ref "C6") (pin "1") (pinfunction "1_1") (pintype "passive"))
      (node (ref "C9") (pin "1") (pinfunction "1_1") (pintype "passive"))
      (node (ref "JP2") (pin "1") (pinfunction "1_1") (pintype "passive"))
      (node (ref "JP3") (pin "1") (pinfunction "1_1") (pintype "passive"))
      (node (ref "U2") (pin "7") (pinfunction "VIN_7") (pintype "passive"))
      (node (ref "U3") (pin "7") (pinfunction "VIN_7") (pintype "passive"))
      (node (ref "U4") (pin "7") (pinfunction "VIN_7") (pintype "passive"))
    )
    (net (code "119") (name "unconnected-(P5-Pad1)") (class "Default")
      (node (ref "P5") (pin "1") (pinfunction "1_1") (pintype "passive+no_connect"))
    )
    (net (code "120") (name "unconnected-(P6-Pad1)") (class "Default")
      (node (ref "P6") (pin "1") (pinfunction "1_1") (pintype "passive+no_connect"))
    )
    (net (code "121") (name "unconnected-(U2-ENA-Pad5)") (class "Default")
      (node (ref "U2") (pin "5") (pinfunction "ENA_5") (pintype "passive+no_connect"))
    )
    (net (code "122") (name "unconnected-(U2-NC-Pad2)") (class "Default")
      (node (ref "U2") (pin "2") (pinfunction "NC_2") (pintype "passive+no_connect"))
    )
    (net (code "123") (name "unconnected-(U2-NC-Pad3)") (class "Default")
      (node (ref "U2") (pin "3") (pinfunction "NC_3") (pintype "passive+no_connect"))
    )
    (net (code "124") (name "unconnected-(U3-ENA-Pad5)") (class "Default")
      (node (ref "U3") (pin "5") (pinfunction "ENA_5") (pintype "passive+no_connect"))
    )
    (net (code "125") (name "unconnected-(U3-NC-Pad2)") (class "Default")
      (node (ref "U3") (pin "2") (pinfunction "NC_2") (pintype "passive+no_connect"))
    )
    (net (code "126") (name "unconnected-(U3-NC-Pad3)") (class "Default")
      (node (ref "U3") (pin "3") (pinfunction "NC_3") (pintype "passive+no_connect"))
    )
    (net (code "127") (name "unconnected-(U4-ENA-Pad5)") (class "Default")
      (node (ref "U4") (pin "5") (pinfunction "ENA_5") (pintype "passive+no_connect"))
    )
    (net (code "128") (name "unconnected-(U4-NC-Pad2)") (class "Default")
      (node (ref "U4") (pin "2") (pinfunction "NC_2") (pintype "passive+no_connect"))
    )
    (net (code "129") (name "unconnected-(U4-NC-Pad3)") (class "Default")
      (node (ref "U4") (pin "3") (pinfunction "NC_3") (pintype "passive+no_connect"))
    )
  )
)
